# automatic_feline_deterrent_2021-05-23.net
KiCad netlist of a schematic drawn in EasyEDA
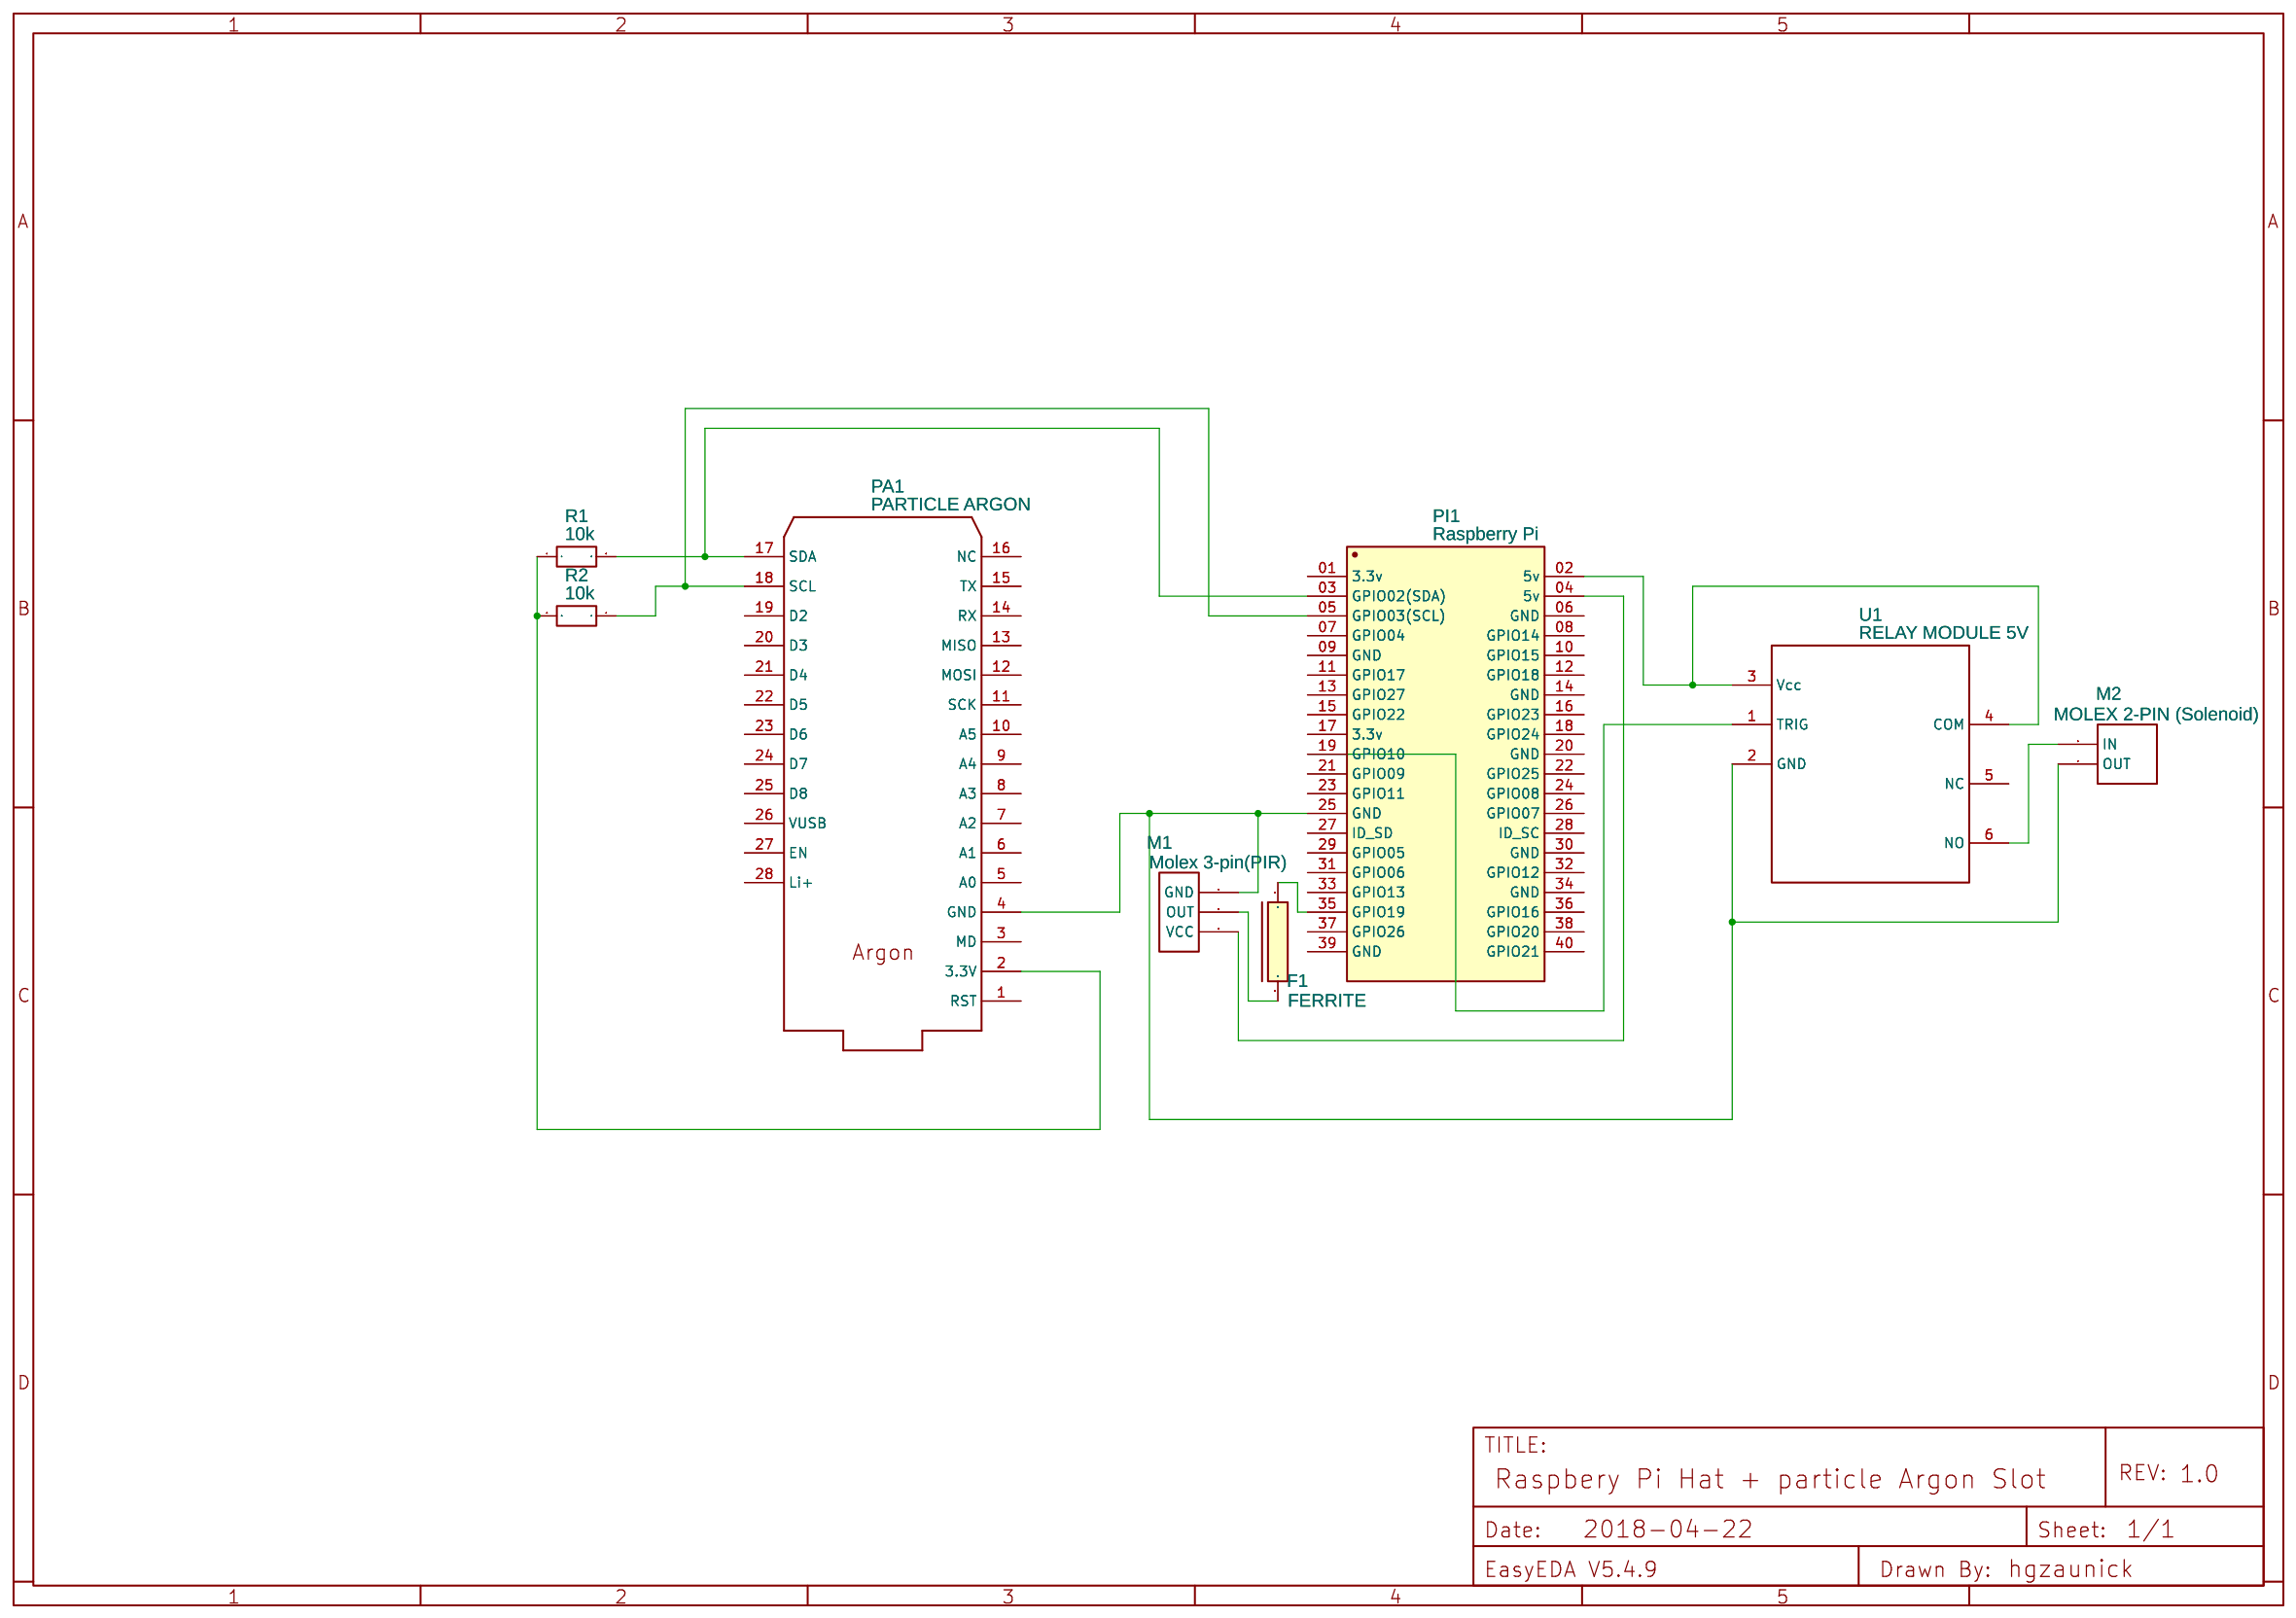
[diagram p0: schematic sheet]

(export (version "E")
  (design (tool "Eeschema 10.0.6"))
  (components
    (comp (ref "F1") (value "FERRITE") (libsource (lib "") (part "FERRITE")))
    (comp (ref "M1")
      (value "Molex 3-pin(PIR)")
      (fields (field (name "BOM_Manufacturer Part") "Molex white 3-pin"))
      (libsource (lib "") (part "Molex white 3-pin"))
    )
    (comp (ref "M2")
      (value "MOLEX 2-PIN (Solenoid)")
      (fields (field (name "BOM_Manufacturer Part") "Molex white 2-pin"))
      (libsource (lib "") (part "MOLEX WHITE 2-PIN"))
    )
    (comp (ref "PA1")
      (value "PARTICLE ARGON")
      (fields (field (name "BOM_Manufacturer Part") "Particle Argon"))
      (libsource (lib "") (part "PARTICLE ARGON"))
    )
    (comp (ref "PI1")
      (value "Raspberry Pi")
      (fields (field (name "BOM_Supplier Part") "485-2222"))
      (libsource (lib "") (part "Raspberry Pi"))
    )
    (comp (ref "R1") (value "10k") (libsource (lib "") (part "R_0603_EU")))
    (comp (ref "R2") (value "10k") (libsource (lib "") (part "R_0603_EU_1")))
    (comp (ref "U1") (value "RELAY MODULE 5V") (libsource (lib "") (part "ARDUINO RELAY MODULE 5V")))
  )
  (nets
    (net (code "1") (name "Net-(M1-GND)") (class "Default")
      (node (ref "M1") (pin "1") (pinfunction "GND_1") (pintype "unspecified"))
      (node (ref "M2") (pin "1") (pinfunction "OUT_1") (pintype "unspecified"))
      (node (ref "PA1") (pin "4") (pinfunction "GND_4") (pintype "unspecified"))
      (node (ref "PI1") (pin "25") (pinfunction "GND_25") (pintype "passive"))
      (node (ref "U1") (pin "2") (pinfunction "GND_2") (pintype "unspecified"))
    )
    (net (code "2") (name "Net-(M1-OUT)") (class "Default")
      (node (ref "F1") (pin "2") (pinfunction "2_2") (pintype "unspecified"))
      (node (ref "M1") (pin "2") (pinfunction "OUT_2") (pintype "unspecified"))
    )
    (net (code "3") (name "Net-(M1-VCC)") (class "Default")
      (node (ref "M1") (pin "3") (pinfunction "VCC_3") (pintype "unspecified"))
      (node (ref "PI1") (pin "04") (pinfunction "5v_04") (pintype "passive"))
    )
    (net (code "4") (name "Net-(M2-IN)") (class "Default")
      (node (ref "M2") (pin "2") (pinfunction "IN_2") (pintype "unspecified"))
      (node (ref "U1") (pin "6") (pinfunction "NO_6") (pintype "unspecified"))
    )
    (net (code "5") (name "Net-(PA1-3.3V)") (class "Default")
      (node (ref "PA1") (pin "2") (pinfunction "3.3V_2") (pintype "unspecified"))
      (node (ref "R1") (pin "1") (pinfunction "1_1") (pintype "unspecified"))
      (node (ref "R2") (pin "2") (pinfunction "2_2") (pintype "unspecified"))
    )
    (net (code "6") (name "Net-(PA1-SCL)") (class "Default")
      (node (ref "PA1") (pin "18") (pinfunction "SCL_18") (pintype "unspecified"))
      (node (ref "PI1") (pin "05") (pinfunction "GPIO03(SCL)_05") (pintype "unspecified"))
      (node (ref "R2") (pin "1") (pinfunction "1_1") (pintype "unspecified"))
    )
    (net (code "7") (name "Net-(PA1-SDA)") (class "Default")
      (node (ref "PA1") (pin "17") (pinfunction "SDA_17") (pintype "unspecified"))
      (node (ref "PI1") (pin "03") (pinfunction "GPIO02(SDA)_03") (pintype "unspecified"))
      (node (ref "R1") (pin "2") (pinfunction "2_2") (pintype "unspecified"))
    )
    (net (code "8") (name "Net-(PI1-GPIO10)") (class "Default")
      (node (ref "PI1") (pin "19") (pinfunction "GPIO10_19") (pintype "unspecified"))
      (node (ref "U1") (pin "1") (pinfunction "TRIG_1") (pintype "unspecified"))
    )
    (net (code "9") (name "Net-(PI1-GPIO19)") (class "Default")
      (node (ref "F1") (pin "1") (pinfunction "1_1") (pintype "unspecified"))
      (node (ref "PI1") (pin "35") (pinfunction "GPIO19_35") (pintype "unspecified"))
    )
    (net (code "10") (name "Net-(U1-COM)") (class "Default")
      (node (ref "PI1") (pin "02") (pinfunction "5v_02") (pintype "passive"))
      (node (ref "U1") (pin "3") (pinfunction "Vcc_3") (pintype "passive"))
      (node (ref "U1") (pin "4") (pinfunction "COM_4") (pintype "unspecified"))
    )
    (net (code "11") (name "unconnected-(PA1-A0-Pad5)") (class "Default")
      (node (ref "PA1") (pin "5") (pinfunction "A0_5") (pintype "unspecified"))
    )
    (net (code "12") (name "unconnected-(PA1-A1-Pad6)") (class "Default")
      (node (ref "PA1") (pin "6") (pinfunction "A1_6") (pintype "unspecified"))
    )
    (net (code "13") (name "unconnected-(PA1-A2-Pad7)") (class "Default")
      (node (ref "PA1") (pin "7") (pinfunction "A2_7") (pintype "unspecified"))
    )
    (net (code "14") (name "unconnected-(PA1-A3-Pad8)") (class "Default")
      (node (ref "PA1") (pin "8") (pinfunction "A3_8") (pintype "unspecified"))
    )
    (net (code "15") (name "unconnected-(PA1-A4-Pad9)") (class "Default")
      (node (ref "PA1") (pin "9") (pinfunction "A4_9") (pintype "unspecified"))
    )
    (net (code "16") (name "unconnected-(PA1-A5-Pad10)") (class "Default")
      (node (ref "PA1") (pin "10") (pinfunction "A5_10") (pintype "unspecified"))
    )
    (net (code "17") (name "unconnected-(PA1-D2-Pad19)") (class "Default")
      (node (ref "PA1") (pin "19") (pinfunction "D2_19") (pintype "unspecified"))
    )
    (net (code "18") (name "unconnected-(PA1-D3-Pad20)") (class "Default")
      (node (ref "PA1") (pin "20") (pinfunction "D3_20") (pintype "unspecified"))
    )
    (net (code "19") (name "unconnected-(PA1-D4-Pad21)") (class "Default")
      (node (ref "PA1") (pin "21") (pinfunction "D4_21") (pintype "unspecified"))
    )
    (net (code "20") (name "unconnected-(PA1-D5-Pad22)") (class "Default")
      (node (ref "PA1") (pin "22") (pinfunction "D5_22") (pintype "unspecified"))
    )
    (net (code "21") (name "unconnected-(PA1-D6-Pad23)") (class "Default")
      (node (ref "PA1") (pin "23") (pinfunction "D6_23") (pintype "unspecified"))
    )
    (net (code "22") (name "unconnected-(PA1-D7-Pad24)") (class "Default")
      (node (ref "PA1") (pin "24") (pinfunction "D7_24") (pintype "unspecified"))
    )
    (net (code "23") (name "unconnected-(PA1-D8-Pad25)") (class "Default")
      (node (ref "PA1") (pin "25") (pinfunction "D8_25") (pintype "unspecified"))
    )
    (net (code "24") (name "unconnected-(PA1-EN-Pad27)") (class "Default")
      (node (ref "PA1") (pin "27") (pinfunction "EN_27") (pintype "unspecified"))
    )
    (net (code "25") (name "unconnected-(PA1-Li+-Pad28)") (class "Default")
      (node (ref "PA1") (pin "28") (pinfunction "Li+_28") (pintype "unspecified"))
    )
    (net (code "26") (name "unconnected-(PA1-MD-Pad3)") (class "Default")
      (node (ref "PA1") (pin "3") (pinfunction "MD_3") (pintype "unspecified"))
    )
    (net (code "27") (name "unconnected-(PA1-MISO-Pad13)") (class "Default")
      (node (ref "PA1") (pin "13") (pinfunction "MISO_13") (pintype "unspecified"))
    )
    (net (code "28") (name "unconnected-(PA1-MOSI-Pad12)") (class "Default")
      (node (ref "PA1") (pin "12") (pinfunction "MOSI_12") (pintype "unspecified"))
    )
    (net (code "29") (name "unconnected-(PA1-NC-Pad16)") (class "Default")
      (node (ref "PA1") (pin "16") (pinfunction "NC_16") (pintype "unspecified"))
    )
    (net (code "30") (name "unconnected-(PA1-RST-Pad1)") (class "Default")
      (node (ref "PA1") (pin "1") (pinfunction "RST_1") (pintype "unspecified"))
    )
    (net (code "31") (name "unconnected-(PA1-RX-Pad14)") (class "Default")
      (node (ref "PA1") (pin "14") (pinfunction "RX_14") (pintype "unspecified"))
    )
    (net (code "32") (name "unconnected-(PA1-SCK-Pad11)") (class "Default")
      (node (ref "PA1") (pin "11") (pinfunction "SCK_11") (pintype "unspecified"))
    )
    (net (code "33") (name "unconnected-(PA1-TX-Pad15)") (class "Default")
      (node (ref "PA1") (pin "15") (pinfunction "TX_15") (pintype "unspecified"))
    )
    (net (code "34") (name "unconnected-(PA1-VUSB-Pad26)") (class "Default")
      (node (ref "PA1") (pin "26") (pinfunction "VUSB_26") (pintype "unspecified"))
    )
    (net (code "35") (name "unconnected-(PI1-3.3v-Pad01)") (class "Default")
      (node (ref "PI1") (pin "01") (pinfunction "3.3v_01") (pintype "passive"))
    )
    (net (code "36") (name "unconnected-(PI1-3.3v-Pad17)") (class "Default")
      (node (ref "PI1") (pin "17") (pinfunction "3.3v_17") (pintype "passive"))
    )
    (net (code "37") (name "unconnected-(PI1-GND-Pad06)") (class "Default")
      (node (ref "PI1") (pin "06") (pinfunction "GND_06") (pintype "passive"))
    )
    (net (code "38") (name "unconnected-(PI1-GND-Pad09)") (class "Default")
      (node (ref "PI1") (pin "09") (pinfunction "GND_09") (pintype "passive"))
    )
    (net (code "39") (name "unconnected-(PI1-GND-Pad14)") (class "Default")
      (node (ref "PI1") (pin "14") (pinfunction "GND_14") (pintype "passive"))
    )
    (net (code "40") (name "unconnected-(PI1-GND-Pad20)") (class "Default")
      (node (ref "PI1") (pin "20") (pinfunction "GND_20") (pintype "passive"))
    )
    (net (code "41") (name "unconnected-(PI1-GND-Pad30)") (class "Default")
      (node (ref "PI1") (pin "30") (pinfunction "GND_30") (pintype "passive"))
    )
    (net (code "42") (name "unconnected-(PI1-GND-Pad34)") (class "Default")
      (node (ref "PI1") (pin "34") (pinfunction "GND_34") (pintype "passive"))
    )
    (net (code "43") (name "unconnected-(PI1-GND-Pad39)") (class "Default")
      (node (ref "PI1") (pin "39") (pinfunction "GND_39") (pintype "passive"))
    )
    (net (code "44") (name "unconnected-(PI1-GPIO04-Pad07)") (class "Default")
      (node (ref "PI1") (pin "07") (pinfunction "GPIO04_07") (pintype "unspecified"))
    )
    (net (code "45") (name "unconnected-(PI1-GPIO05-Pad29)") (class "Default")
      (node (ref "PI1") (pin "29") (pinfunction "GPIO05_29") (pintype "unspecified"))
    )
    (net (code "46") (name "unconnected-(PI1-GPIO06-Pad31)") (class "Default")
      (node (ref "PI1") (pin "31") (pinfunction "GPIO06_31") (pintype "unspecified"))
    )
    (net (code "47") (name "unconnected-(PI1-GPIO07-Pad26)") (class "Default")
      (node (ref "PI1") (pin "26") (pinfunction "GPIO07_26") (pintype "unspecified"))
    )
    (net (code "48") (name "unconnected-(PI1-GPIO08-Pad24)") (class "Default")
      (node (ref "PI1") (pin "24") (pinfunction "GPIO08_24") (pintype "unspecified"))
    )
    (net (code "49") (name "unconnected-(PI1-GPIO09-Pad21)") (class "Default")
      (node (ref "PI1") (pin "21") (pinfunction "GPIO09_21") (pintype "unspecified"))
    )
    (net (code "50") (name "unconnected-(PI1-GPIO11-Pad23)") (class "Default")
      (node (ref "PI1") (pin "23") (pinfunction "GPIO11_23") (pintype "unspecified"))
    )
    (net (code "51") (name "unconnected-(PI1-GPIO12-Pad32)") (class "Default")
      (node (ref "PI1") (pin "32") (pinfunction "GPIO12_32") (pintype "unspecified"))
    )
    (net (code "52") (name "unconnected-(PI1-GPIO13-Pad33)") (class "Default")
      (node (ref "PI1") (pin "33") (pinfunction "GPIO13_33") (pintype "unspecified"))
    )
    (net (code "53") (name "unconnected-(PI1-GPIO14-Pad08)") (class "Default")
      (node (ref "PI1") (pin "08") (pinfunction "GPIO14_08") (pintype "unspecified"))
    )
    (net (code "54") (name "unconnected-(PI1-GPIO15-Pad10)") (class "Default")
      (node (ref "PI1") (pin "10") (pinfunction "GPIO15_10") (pintype "unspecified"))
    )
    (net (code "55") (name "unconnected-(PI1-GPIO16-Pad36)") (class "Default")
      (node (ref "PI1") (pin "36") (pinfunction "GPIO16_36") (pintype "unspecified"))
    )
    (net (code "56") (name "unconnected-(PI1-GPIO17-Pad11)") (class "Default")
      (node (ref "PI1") (pin "11") (pinfunction "GPIO17_11") (pintype "unspecified"))
    )
    (net (code "57") (name "unconnected-(PI1-GPIO18-Pad12)") (class "Default")
      (node (ref "PI1") (pin "12") (pinfunction "GPIO18_12") (pintype "unspecified"))
    )
    (net (code "58") (name "unconnected-(PI1-GPIO20-Pad38)") (class "Default")
      (node (ref "PI1") (pin "38") (pinfunction "GPIO20_38") (pintype "unspecified"))
    )
    (net (code "59") (name "unconnected-(PI1-GPIO21-Pad40)") (class "Default")
      (node (ref "PI1") (pin "40") (pinfunction "GPIO21_40") (pintype "unspecified"))
    )
    (net (code "60") (name "unconnected-(PI1-GPIO22-Pad15)") (class "Default")
      (node (ref "PI1") (pin "15") (pinfunction "GPIO22_15") (pintype "unspecified"))
    )
    (net (code "61") (name "unconnected-(PI1-GPIO23-Pad16)") (class "Default")
      (node (ref "PI1") (pin "16") (pinfunction "GPIO23_16") (pintype "unspecified"))
    )
    (net (code "62") (name "unconnected-(PI1-GPIO24-Pad18)") (class "Default")
      (node (ref "PI1") (pin "18") (pinfunction "GPIO24_18") (pintype "unspecified"))
    )
    (net (code "63") (name "unconnected-(PI1-GPIO25-Pad22)") (class "Default")
      (node (ref "PI1") (pin "22") (pinfunction "GPIO25_22") (pintype "unspecified"))
    )
    (net (code "64") (name "unconnected-(PI1-GPIO26-Pad37)") (class "Default")
      (node (ref "PI1") (pin "37") (pinfunction "GPIO26_37") (pintype "unspecified"))
    )
    (net (code "65") (name "unconnected-(PI1-GPIO27-Pad13)") (class "Default")
      (node (ref "PI1") (pin "13") (pinfunction "GPIO27_13") (pintype "unspecified"))
    )
    (net (code "66") (name "unconnected-(PI1-ID_SC-Pad28)") (class "Default")
      (node (ref "PI1") (pin "28") (pinfunction "ID_SC_28") (pintype "unspecified"))
    )
    (net (code "67") (name "unconnected-(PI1-ID_SD-Pad27)") (class "Default")
      (node (ref "PI1") (pin "27") (pinfunction "ID_SD_27") (pintype "unspecified"))
    )
    (net (code "68") (name "unconnected-(U1-NC-Pad5)") (class "Default")
      (node (ref "U1") (pin "5") (pinfunction "NC_5") (pintype "unspecified"))
    )
  )
)
